# Stabilizer_Pounder.net
KiCad netlist of a schematic drawn in Altium Designer
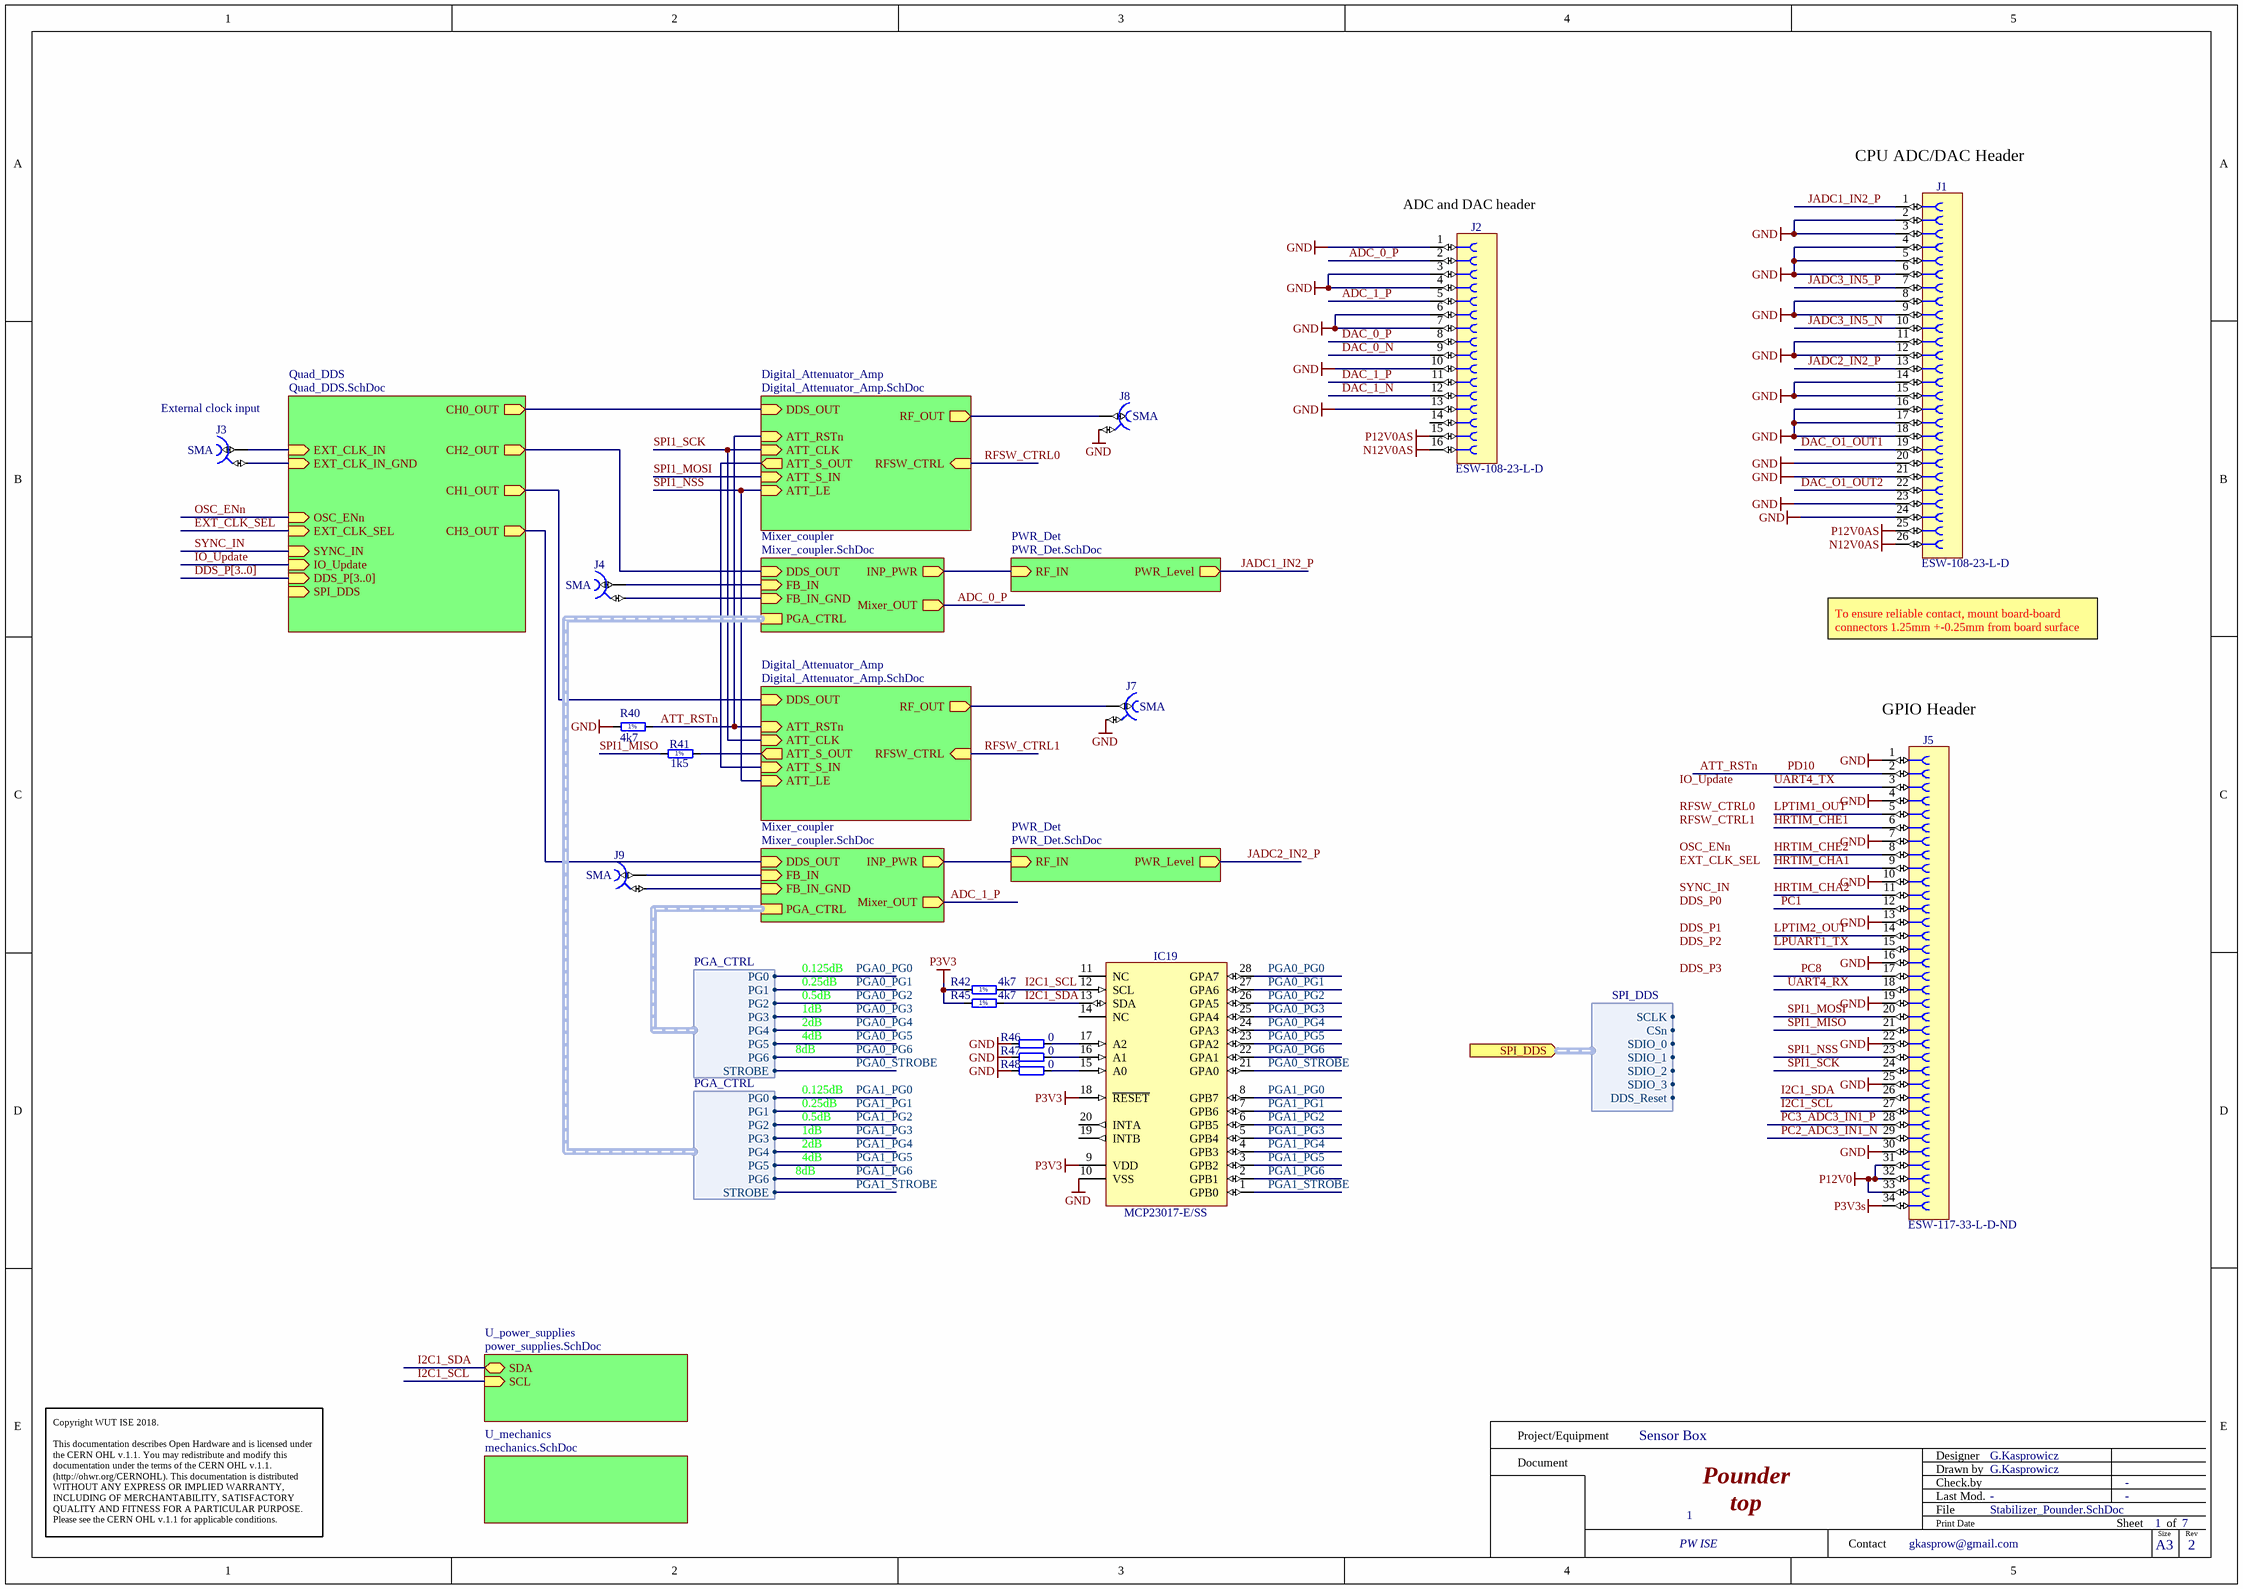
[diagram p0: Stabilizer_Pounder.SchDoc]

(export (version "E")
  (design (tool "Eeschema 10.0.6"))
  (components
    (comp (ref "IC19")
      (value "MCP23017-E/SS")
      (footprint "SOP65P780X200-28N")
      (description "16-bit I/O Port Expander With Serial Interface")
      (fields (field (name "MANUFACTURER") "MICROCHIP TECHNOLOGY") (field (name "AUTHOR") "CERN DEM JLC"))
      (libsource (lib "ICs And Semiconductors") (part "MCP23017-E/SS"))
    )
    (comp (ref "J1")
      (value "ESW-108-23-L-D")
      (footprint "connectors:ESW-113-23-L-D")
      (description "Connector Elevated Socket 26 POS 2.54mm, 13.59mm height")
      (fields
        (field (name "MANUFACTURER") "Samtec")
        (field (name "MANUFACTURER PART NUMBER") "ESW-108-23-L-D")
      )
      (libsource (lib "connectors") (part "ESW-113-23-L-D"))
    )
    (comp (ref "J2")
      (value "ESW-108-23-L-D")
      (footprint "connectors:ESW-108-23-L-D")
      (description "Connector Elevated Socket 16 POS 2.54mm, 13.59mm height")
      (fields
        (field (name "MANUFACTURER") "Samtec")
        (field (name "MANUFACTURER PART NUMBER") "ESW-108-23-L-D")
      )
      (libsource (lib "connectors") (part "ESW-108-23-L-D"))
    )
    (comp (ref "J3")
      (value "SMA")
      (footprint "RF249BT0050GHDW")
      (description "50 Ohm Through Hole SMA Right Angle PCB Jack")
      (fields
        (field (name "PART NUMBER") "AdamTech_RF249BT0050GHDW")
        (field (name "MANUFACTURER") "AdamTech")
        (field (name "AUTHOR") "GK")
      )
      (libsource (lib "") (part "CON_SMA_RF249BT0050GHDW_1"))
    )
    (comp (ref "J4")
      (value "SMA")
      (footprint "RF249BT0050GHDW")
      (description "50 Ohm Through Hole SMA Right Angle PCB Jack")
      (fields
        (field (name "PART NUMBER") "AdamTech_RF249BT0050GHDW")
        (field (name "MANUFACTURER") "AdamTech")
        (field (name "AUTHOR") "GK")
      )
      (libsource (lib "") (part "CON_SMA_RF249BT0050GHDW_1"))
    )
    (comp (ref "J5")
      (value "ESW-108-23-L-D")
      (footprint "connectors:ESW-117-23-L-D")
      (description "Connector Elevated Socket 34 POS 2.54mm, 13.59mm height")
      (fields
        (field (name "MANUFACTURER") "Samtec")
        (field (name "MANUFACTURER PART NUMBER") "ESW-117-33-L-D-ND")
      )
      (libsource (lib "connectors") (part "ESW-117-23-L-D"))
    )
    (comp (ref "J7")
      (value "SMA")
      (footprint "RF249BT0050GHDW")
      (description "50 Ohm Through Hole SMA Right Angle PCB Jack")
      (fields
        (field (name "PART NUMBER") "AdamTech_RF249BT0050GHDW")
        (field (name "MANUFACTURER") "AdamTech")
        (field (name "AUTHOR") "GK")
      )
      (libsource (lib "LIBRARY_SCH") (part "CON_SMA_RF249BT0050GHDW"))
    )
    (comp (ref "J8")
      (value "SMA")
      (footprint "RF249BT0050GHDW")
      (description "50 Ohm Through Hole SMA Right Angle PCB Jack")
      (fields
        (field (name "PART NUMBER") "AdamTech_RF249BT0050GHDW")
        (field (name "MANUFACTURER") "AdamTech")
        (field (name "AUTHOR") "GK")
      )
      (libsource (lib "LIBRARY_SCH") (part "CON_SMA_RF249BT0050GHDW"))
    )
    (comp (ref "J9")
      (value "SMA")
      (footprint "RF249BT0050GHDW")
      (description "50 Ohm Through Hole SMA Right Angle PCB Jack")
      (fields
        (field (name "PART NUMBER") "AdamTech_RF249BT0050GHDW")
        (field (name "MANUFACTURER") "AdamTech")
        (field (name "AUTHOR") "GK")
      )
      (libsource (lib "") (part "CON_SMA_RF249BT0050GHDW_1"))
    )
    (comp (ref "R40")
      (value "4k7")
      (footprint "RESC1005X40N")
      (description "Resistor - 1%")
      (fields
        (field (name "PART NUMBER") "R0402_4K7_1%_0.0625W_100PPM")
        (field (name "POWER") "0.0625W")
        (field (name "AUTHOR") "CERN DEM JLC")
      )
      (libsource (lib "Resistors") (part "Resistor - 1%"))
    )
    (comp (ref "R41")
      (value "1k5")
      (footprint "RESC1005X40N")
      (description "Resistor - 1%")
      (fields
        (field (name "PART NUMBER") "R0402_1K5_1%_0.0625W_100PPM")
        (field (name "POWER") "0.0625W")
        (field (name "AUTHOR") "CERN DEM JLC")
      )
      (libsource (lib "Resistors") (part "Resistor - 1%"))
    )
    (comp (ref "R42")
      (value "4k7")
      (footprint "RESC1005X40N")
      (description "Resistor - 1%")
      (fields
        (field (name "PART NUMBER") "R0402_4K7_1%_0.0625W_100PPM")
        (field (name "POWER") "0.0625W")
        (field (name "AUTHOR") "CERN DEM JLC")
      )
      (libsource (lib "Resistors") (part "Resistor - 1%"))
    )
    (comp (ref "R45")
      (value "4k7")
      (footprint "RESC1005X40N")
      (description "Resistor - 1%")
      (fields
        (field (name "PART NUMBER") "R0402_4K7_1%_0.0625W_100PPM")
        (field (name "POWER") "0.0625W")
        (field (name "AUTHOR") "CERN DEM JLC")
      )
      (libsource (lib "Resistors") (part "Resistor - 1%"))
    )
    (comp (ref "R46")
      (value "0")
      (footprint "RESC1005X40N")
      (description "Resistor")
      (fields
        (field (name "PART NUMBER") "R0402_0R_JUMPER")
        (field (name "MANUFACTURER") "GENERIC")
        (field (name "AUTHOR") "CERN DEM JLC")
      )
      (libsource (lib "Resistors") (part "Resistor"))
    )
    (comp (ref "R47")
      (value "0")
      (footprint "RESC1005X40N")
      (description "Resistor")
      (fields
        (field (name "PART NUMBER") "R0402_0R_JUMPER")
        (field (name "MANUFACTURER") "GENERIC")
        (field (name "AUTHOR") "CERN DEM JLC")
      )
      (libsource (lib "Resistors") (part "Resistor"))
    )
    (comp (ref "R48")
      (value "0")
      (footprint "RESC1005X40N")
      (description "Resistor")
      (fields
        (field (name "PART NUMBER") "R0402_0R_JUMPER")
        (field (name "MANUFACTURER") "GENERIC")
        (field (name "AUTHOR") "CERN DEM JLC")
      )
      (libsource (lib "Resistors") (part "Resistor"))
    )
  )
  (nets
    (net (code "3") (name "/ADC_0_P") (class "Default")
      (node (ref "J2") (pin "2") (pinfunction "2_2") (pintype "bidirectional"))
    )
    (net (code "4") (name "/ADC_1_P") (class "Default")
      (node (ref "J2") (pin "5") (pinfunction "5_5") (pintype "bidirectional"))
    )
    (net (code "5") (name "/ATT_RSTn") (class "Default")
      (node (ref "J5") (pin "2") (pinfunction "2_2") (pintype "bidirectional"))
      (node (ref "R40") (pin "2") (pinfunction "2_2") (pintype "passive"))
    )
    (net (code "6") (name "/ATT_S_OUT") (class "Default")
      (node (ref "R41") (pin "2") (pinfunction "2_2") (pintype "passive"))
    )
    (net (code "12") (name "/DAC_0_N") (class "Default")
      (node (ref "J2") (pin "9") (pinfunction "9_9") (pintype "bidirectional"))
    )
    (net (code "13") (name "/DAC_0_P") (class "Default")
      (node (ref "J2") (pin "8") (pinfunction "8_8") (pintype "bidirectional"))
    )
    (net (code "14") (name "/DAC_1_N") (class "Default")
      (node (ref "J2") (pin "12") (pinfunction "12_12") (pintype "bidirectional"))
    )
    (net (code "15") (name "/DAC_1_P") (class "Default")
      (node (ref "J2") (pin "11") (pinfunction "11_11") (pintype "bidirectional"))
    )
    (net (code "16") (name "/DAC_O1_OUT1") (class "Default")
      (node (ref "J1") (pin "19") (pinfunction "19_19") (pintype "bidirectional"))
    )
    (net (code "17") (name "/DAC_O1_OUT2") (class "Default")
      (node (ref "J1") (pin "22") (pinfunction "22_22") (pintype "bidirectional"))
    )
    (net (code "23") (name "/EXT_CLK_IN") (class "Default")
      (node (ref "J3") (pin "1") (pinfunction "1_1") (pintype "bidirectional"))
    )
    (net (code "24") (name "/EXT_CLK_IN_GND") (class "Default")
      (node (ref "J3") (pin "2") (pinfunction "2_2") (pintype "bidirectional"))
    )
    (net (code "26") (name "/FB_IN") (class "Default")
      (node (ref "J9") (pin "1") (pinfunction "1_1") (pintype "bidirectional"))
    )
    (net (code "27") (name "/FB_IN_1") (class "Default")
      (node (ref "J4") (pin "1") (pinfunction "1_1") (pintype "bidirectional"))
    )
    (net (code "28") (name "/FB_IN_GND") (class "Default")
      (node (ref "J9") (pin "2") (pinfunction "2_2") (pintype "bidirectional"))
    )
    (net (code "29") (name "/FB_IN_GND_1") (class "Default")
      (node (ref "J4") (pin "2") (pinfunction "2_2") (pintype "bidirectional"))
    )
    (net (code "30") (name "/HRTIM_CHA1") (class "Default")
      (node (ref "J5") (pin "9") (pinfunction "9_9") (pintype "bidirectional"))
    )
    (net (code "31") (name "/HRTIM_CHA2") (class "Default")
      (node (ref "J5") (pin "11") (pinfunction "11_11") (pintype "bidirectional"))
    )
    (net (code "32") (name "/HRTIM_CHE1") (class "Default")
      (node (ref "J5") (pin "6") (pinfunction "6_6") (pintype "bidirectional"))
    )
    (net (code "33") (name "/HRTIM_CHE2") (class "Default")
      (node (ref "J5") (pin "8") (pinfunction "8_8") (pintype "bidirectional"))
    )
    (net (code "34") (name "/I2C1_SCL") (class "Default")
      (node (ref "IC19") (pin "12") (pinfunction "SCL_12") (pintype "input"))
      (node (ref "J5") (pin "27") (pinfunction "27_27") (pintype "bidirectional"))
      (node (ref "R42") (pin "2") (pinfunction "2_2") (pintype "passive"))
    )
    (net (code "35") (name "/I2C1_SDA") (class "Default")
      (node (ref "IC19") (pin "13") (pinfunction "SDA_13") (pintype "bidirectional"))
      (node (ref "J5") (pin "26") (pinfunction "26_26") (pintype "bidirectional"))
      (node (ref "R45") (pin "2") (pinfunction "2_2") (pintype "passive"))
    )
    (net (code "39") (name "/JADC1_IN2_P") (class "Default")
      (node (ref "J1") (pin "1") (pinfunction "1_1") (pintype "bidirectional"))
    )
    (net (code "40") (name "/JADC2_IN2_P") (class "Default")
      (node (ref "J1") (pin "13") (pinfunction "13_13") (pintype "bidirectional"))
    )
    (net (code "41") (name "/JADC3_IN5_N") (class "Default")
      (node (ref "J1") (pin "10") (pinfunction "10_10") (pintype "bidirectional"))
    )
    (net (code "42") (name "/JADC3_IN5_P") (class "Default")
      (node (ref "J1") (pin "7") (pinfunction "7_7") (pintype "bidirectional"))
    )
    (net (code "43") (name "/LPTIM1_OUT") (class "Default")
      (node (ref "J5") (pin "5") (pinfunction "5_5") (pintype "bidirectional"))
    )
    (net (code "44") (name "/LPTIM2_OUT") (class "Default")
      (node (ref "J5") (pin "14") (pinfunction "14_14") (pintype "bidirectional"))
    )
    (net (code "45") (name "/LPUART1_TX") (class "Default")
      (node (ref "J5") (pin "15") (pinfunction "15_15") (pintype "bidirectional"))
    )
    (net (code "47") (name "/PC1") (class "Default")
      (node (ref "J5") (pin "12") (pinfunction "12_12") (pintype "bidirectional"))
    )
    (net (code "48") (name "/PC2_ADC3_IN1_N") (class "Default")
      (node (ref "J5") (pin "29") (pinfunction "29_29") (pintype "bidirectional"))
    )
    (net (code "49") (name "/PC3_ADC3_IN1_P") (class "Default")
      (node (ref "J5") (pin "28") (pinfunction "28_28") (pintype "bidirectional"))
    )
    (net (code "50") (name "/PC8") (class "Default")
      (node (ref "J5") (pin "17") (pinfunction "17_17") (pintype "bidirectional"))
    )
    (net (code "51") (name "/PGA0_PG0") (class "Default")
      (node (ref "IC19") (pin "28") (pinfunction "GPA7_28") (pintype "bidirectional"))
    )
    (net (code "52") (name "/PGA0_PG1") (class "Default")
      (node (ref "IC19") (pin "27") (pinfunction "GPA6_27") (pintype "bidirectional"))
    )
    (net (code "53") (name "/PGA0_PG2") (class "Default")
      (node (ref "IC19") (pin "26") (pinfunction "GPA5_26") (pintype "bidirectional"))
    )
    (net (code "54") (name "/PGA0_PG3") (class "Default")
      (node (ref "IC19") (pin "25") (pinfunction "GPA4_25") (pintype "bidirectional"))
    )
    (net (code "55") (name "/PGA0_PG4") (class "Default")
      (node (ref "IC19") (pin "24") (pinfunction "GPA3_24") (pintype "bidirectional"))
    )
    (net (code "56") (name "/PGA0_PG5") (class "Default")
      (node (ref "IC19") (pin "23") (pinfunction "GPA2_23") (pintype "bidirectional"))
    )
    (net (code "57") (name "/PGA0_PG6") (class "Default")
      (node (ref "IC19") (pin "22") (pinfunction "GPA1_22") (pintype "bidirectional"))
    )
    (net (code "58") (name "/PGA0_STROBE") (class "Default")
      (node (ref "IC19") (pin "21") (pinfunction "GPA0_21") (pintype "bidirectional"))
    )
    (net (code "59") (name "/PGA1_PG0") (class "Default")
      (node (ref "IC19") (pin "8") (pinfunction "GPB7_8") (pintype "bidirectional"))
    )
    (net (code "60") (name "/PGA1_PG1") (class "Default")
      (node (ref "IC19") (pin "7") (pinfunction "GPB6_7") (pintype "bidirectional"))
    )
    (net (code "61") (name "/PGA1_PG2") (class "Default")
      (node (ref "IC19") (pin "6") (pinfunction "GPB5_6") (pintype "bidirectional"))
    )
    (net (code "62") (name "/PGA1_PG3") (class "Default")
      (node (ref "IC19") (pin "5") (pinfunction "GPB4_5") (pintype "bidirectional"))
    )
    (net (code "63") (name "/PGA1_PG4") (class "Default")
      (node (ref "IC19") (pin "4") (pinfunction "GPB3_4") (pintype "bidirectional"))
    )
    (net (code "64") (name "/PGA1_PG5") (class "Default")
      (node (ref "IC19") (pin "3") (pinfunction "GPB2_3") (pintype "bidirectional"))
    )
    (net (code "65") (name "/PGA1_PG6") (class "Default")
      (node (ref "IC19") (pin "2") (pinfunction "GPB1_2") (pintype "bidirectional"))
    )
    (net (code "66") (name "/PGA1_STROBE") (class "Default")
      (node (ref "IC19") (pin "1") (pinfunction "GPB0_1") (pintype "bidirectional"))
    )
    (net (code "69") (name "/RF_OUT") (class "Default")
      (node (ref "J8") (pin "1") (pinfunction "1_1") (pintype "bidirectional"))
    )
    (net (code "70") (name "/RF_OUT_1") (class "Default")
      (node (ref "J7") (pin "1") (pinfunction "1_1") (pintype "bidirectional"))
    )
    (net (code "71") (name "/SPI1_MISO") (class "Default")
      (node (ref "J5") (pin "21") (pinfunction "21_21") (pintype "bidirectional"))
      (node (ref "R41") (pin "1") (pinfunction "1_1") (pintype "passive"))
    )
    (net (code "72") (name "/SPI1_MOSI") (class "Default")
      (node (ref "J5") (pin "20") (pinfunction "20_20") (pintype "bidirectional"))
    )
    (net (code "73") (name "/SPI1_NSS") (class "Default")
      (node (ref "J5") (pin "23") (pinfunction "23_23") (pintype "bidirectional"))
    )
    (net (code "74") (name "/SPI1_SCK") (class "Default")
      (node (ref "J5") (pin "24") (pinfunction "24_24") (pintype "bidirectional"))
    )
    (net (code "76") (name "/UART4_RX") (class "Default")
      (node (ref "J5") (pin "18") (pinfunction "18_18") (pintype "bidirectional"))
    )
    (net (code "77") (name "/UART4_TX") (class "Default")
      (node (ref "J5") (pin "3") (pinfunction "3_3") (pintype "bidirectional"))
    )
    (net (code "80") (name "GND") (class "Default")
      (node (ref "IC19") (pin "10") (pinfunction "VSS_10") (pintype "power_in"))
      (node (ref "J1") (pin "11") (pinfunction "11_11") (pintype "bidirectional"))
      (node (ref "J1") (pin "12") (pinfunction "12_12") (pintype "bidirectional"))
      (node (ref "J1") (pin "14") (pinfunction "14_14") (pintype "bidirectional"))
      (node (ref "J1") (pin "15") (pinfunction "15_15") (pintype "bidirectional"))
      (node (ref "J1") (pin "16") (pinfunction "16_16") (pintype "bidirectional"))
      (node (ref "J1") (pin "17") (pinfunction "17_17") (pintype "bidirectional"))
      (node (ref "J1") (pin "18") (pinfunction "18_18") (pintype "bidirectional"))
      (node (ref "J1") (pin "2") (pinfunction "2_2") (pintype "bidirectional"))
      (node (ref "J1") (pin "20") (pinfunction "20_20") (pintype "bidirectional"))
      (node (ref "J1") (pin "21") (pinfunction "21_21") (pintype "bidirectional"))
      (node (ref "J1") (pin "23") (pinfunction "23_23") (pintype "bidirectional"))
      (node (ref "J1") (pin "24") (pinfunction "24_24") (pintype "bidirectional"))
      (node (ref "J1") (pin "3") (pinfunction "3_3") (pintype "bidirectional"))
      (node (ref "J1") (pin "4") (pinfunction "4_4") (pintype "bidirectional"))
      (node (ref "J1") (pin "5") (pinfunction "5_5") (pintype "bidirectional"))
      (node (ref "J1") (pin "6") (pinfunction "6_6") (pintype "bidirectional"))
      (node (ref "J1") (pin "8") (pinfunction "8_8") (pintype "bidirectional"))
      (node (ref "J1") (pin "9") (pinfunction "9_9") (pintype "bidirectional"))
      (node (ref "J2") (pin "1") (pinfunction "1_1") (pintype "bidirectional"))
      (node (ref "J2") (pin "10") (pinfunction "10_10") (pintype "bidirectional"))
      (node (ref "J2") (pin "13") (pinfunction "13_13") (pintype "bidirectional"))
      (node (ref "J2") (pin "3") (pinfunction "3_3") (pintype "bidirectional"))
      (node (ref "J2") (pin "4") (pinfunction "4_4") (pintype "bidirectional"))
      (node (ref "J2") (pin "6") (pinfunction "6_6") (pintype "bidirectional"))
      (node (ref "J2") (pin "7") (pinfunction "7_7") (pintype "bidirectional"))
      (node (ref "J5") (pin "1") (pinfunction "1_1") (pintype "bidirectional"))
      (node (ref "J5") (pin "10") (pinfunction "10_10") (pintype "bidirectional"))
      (node (ref "J5") (pin "13") (pinfunction "13_13") (pintype "bidirectional"))
      (node (ref "J5") (pin "16") (pinfunction "16_16") (pintype "bidirectional"))
      (node (ref "J5") (pin "19") (pinfunction "19_19") (pintype "bidirectional"))
      (node (ref "J5") (pin "22") (pinfunction "22_22") (pintype "bidirectional"))
      (node (ref "J5") (pin "25") (pinfunction "25_25") (pintype "bidirectional"))
      (node (ref "J5") (pin "30") (pinfunction "30_30") (pintype "bidirectional"))
      (node (ref "J5") (pin "4") (pinfunction "4_4") (pintype "bidirectional"))
      (node (ref "J5") (pin "7") (pinfunction "7_7") (pintype "bidirectional"))
      (node (ref "J7") (pin "2") (pinfunction "2_2") (pintype "bidirectional"))
      (node (ref "J8") (pin "2") (pinfunction "2_2") (pintype "bidirectional"))
      (node (ref "R40") (pin "1") (pinfunction "1_1") (pintype "passive"))
      (node (ref "R46") (pin "1") (pinfunction "1_1") (pintype "passive"))
      (node (ref "R47") (pin "1") (pinfunction "1_1") (pintype "passive"))
      (node (ref "R48") (pin "1") (pinfunction "1_1") (pintype "passive"))
    )
    (net (code "81") (name "N12V0AS") (class "Default")
      (node (ref "J1") (pin "26") (pinfunction "26_26") (pintype "bidirectional"))
      (node (ref "J2") (pin "16") (pinfunction "16_16") (pintype "bidirectional"))
    )
    (net (code "82") (name "Net-(IC19-A0)") (class "Default")
      (node (ref "IC19") (pin "15") (pinfunction "A0_15") (pintype "input"))
      (node (ref "R48") (pin "2") (pinfunction "2_2") (pintype "passive"))
    )
    (net (code "83") (name "Net-(IC19-A1)") (class "Default")
      (node (ref "IC19") (pin "16") (pinfunction "A1_16") (pintype "input"))
      (node (ref "R47") (pin "2") (pinfunction "2_2") (pintype "passive"))
    )
    (net (code "84") (name "Net-(IC19-A2)") (class "Default")
      (node (ref "IC19") (pin "17") (pinfunction "A2_17") (pintype "input"))
      (node (ref "R46") (pin "2") (pinfunction "2_2") (pintype "passive"))
    )
    (net (code "85") (name "P3V3") (class "Default")
      (node (ref "IC19") (pin "18") (pinfunction "~{RESET}_18") (pintype "input"))
      (node (ref "IC19") (pin "9") (pinfunction "VDD_9") (pintype "power_in"))
      (node (ref "R42") (pin "1") (pinfunction "1_1") (pintype "passive"))
      (node (ref "R45") (pin "1") (pinfunction "1_1") (pintype "passive"))
    )
    (net (code "86") (name "P3V3s") (class "Default")
      (node (ref "J5") (pin "34") (pinfunction "34_34") (pintype "bidirectional"))
    )
    (net (code "87") (name "P12V0") (class "Default")
      (node (ref "J5") (pin "31") (pinfunction "31_31") (pintype "bidirectional"))
      (node (ref "J5") (pin "32") (pinfunction "32_32") (pintype "bidirectional"))
      (node (ref "J5") (pin "33") (pinfunction "33_33") (pintype "bidirectional"))
    )
    (net (code "88") (name "P12V0AS") (class "Default")
      (node (ref "J1") (pin "25") (pinfunction "25_25") (pintype "bidirectional"))
      (node (ref "J2") (pin "15") (pinfunction "15_15") (pintype "bidirectional"))
    )
    (net (code "89") (name "unconnected-(IC19-INTA-Pad20)") (class "Default")
      (node (ref "IC19") (pin "20") (pinfunction "INTA_20") (pintype "output"))
    )
    (net (code "90") (name "unconnected-(IC19-INTB-Pad19)") (class "Default")
      (node (ref "IC19") (pin "19") (pinfunction "INTB_19") (pintype "output"))
    )
    (net (code "91") (name "unconnected-(IC19-NC-Pad11)") (class "Default")
      (node (ref "IC19") (pin "11") (pinfunction "NC_11") (pintype "passive"))
    )
    (net (code "92") (name "unconnected-(IC19-NC-Pad14)") (class "Default")
      (node (ref "IC19") (pin "14") (pinfunction "NC_14") (pintype "passive"))
    )
    (net (code "93") (name "unconnected-(J2-Pad14)") (class "Default")
      (node (ref "J2") (pin "14") (pinfunction "14_14") (pintype "bidirectional"))
    )
  )
)
